# MM2_plates.net
KiCad netlist of a schematic drawn in EAGLE
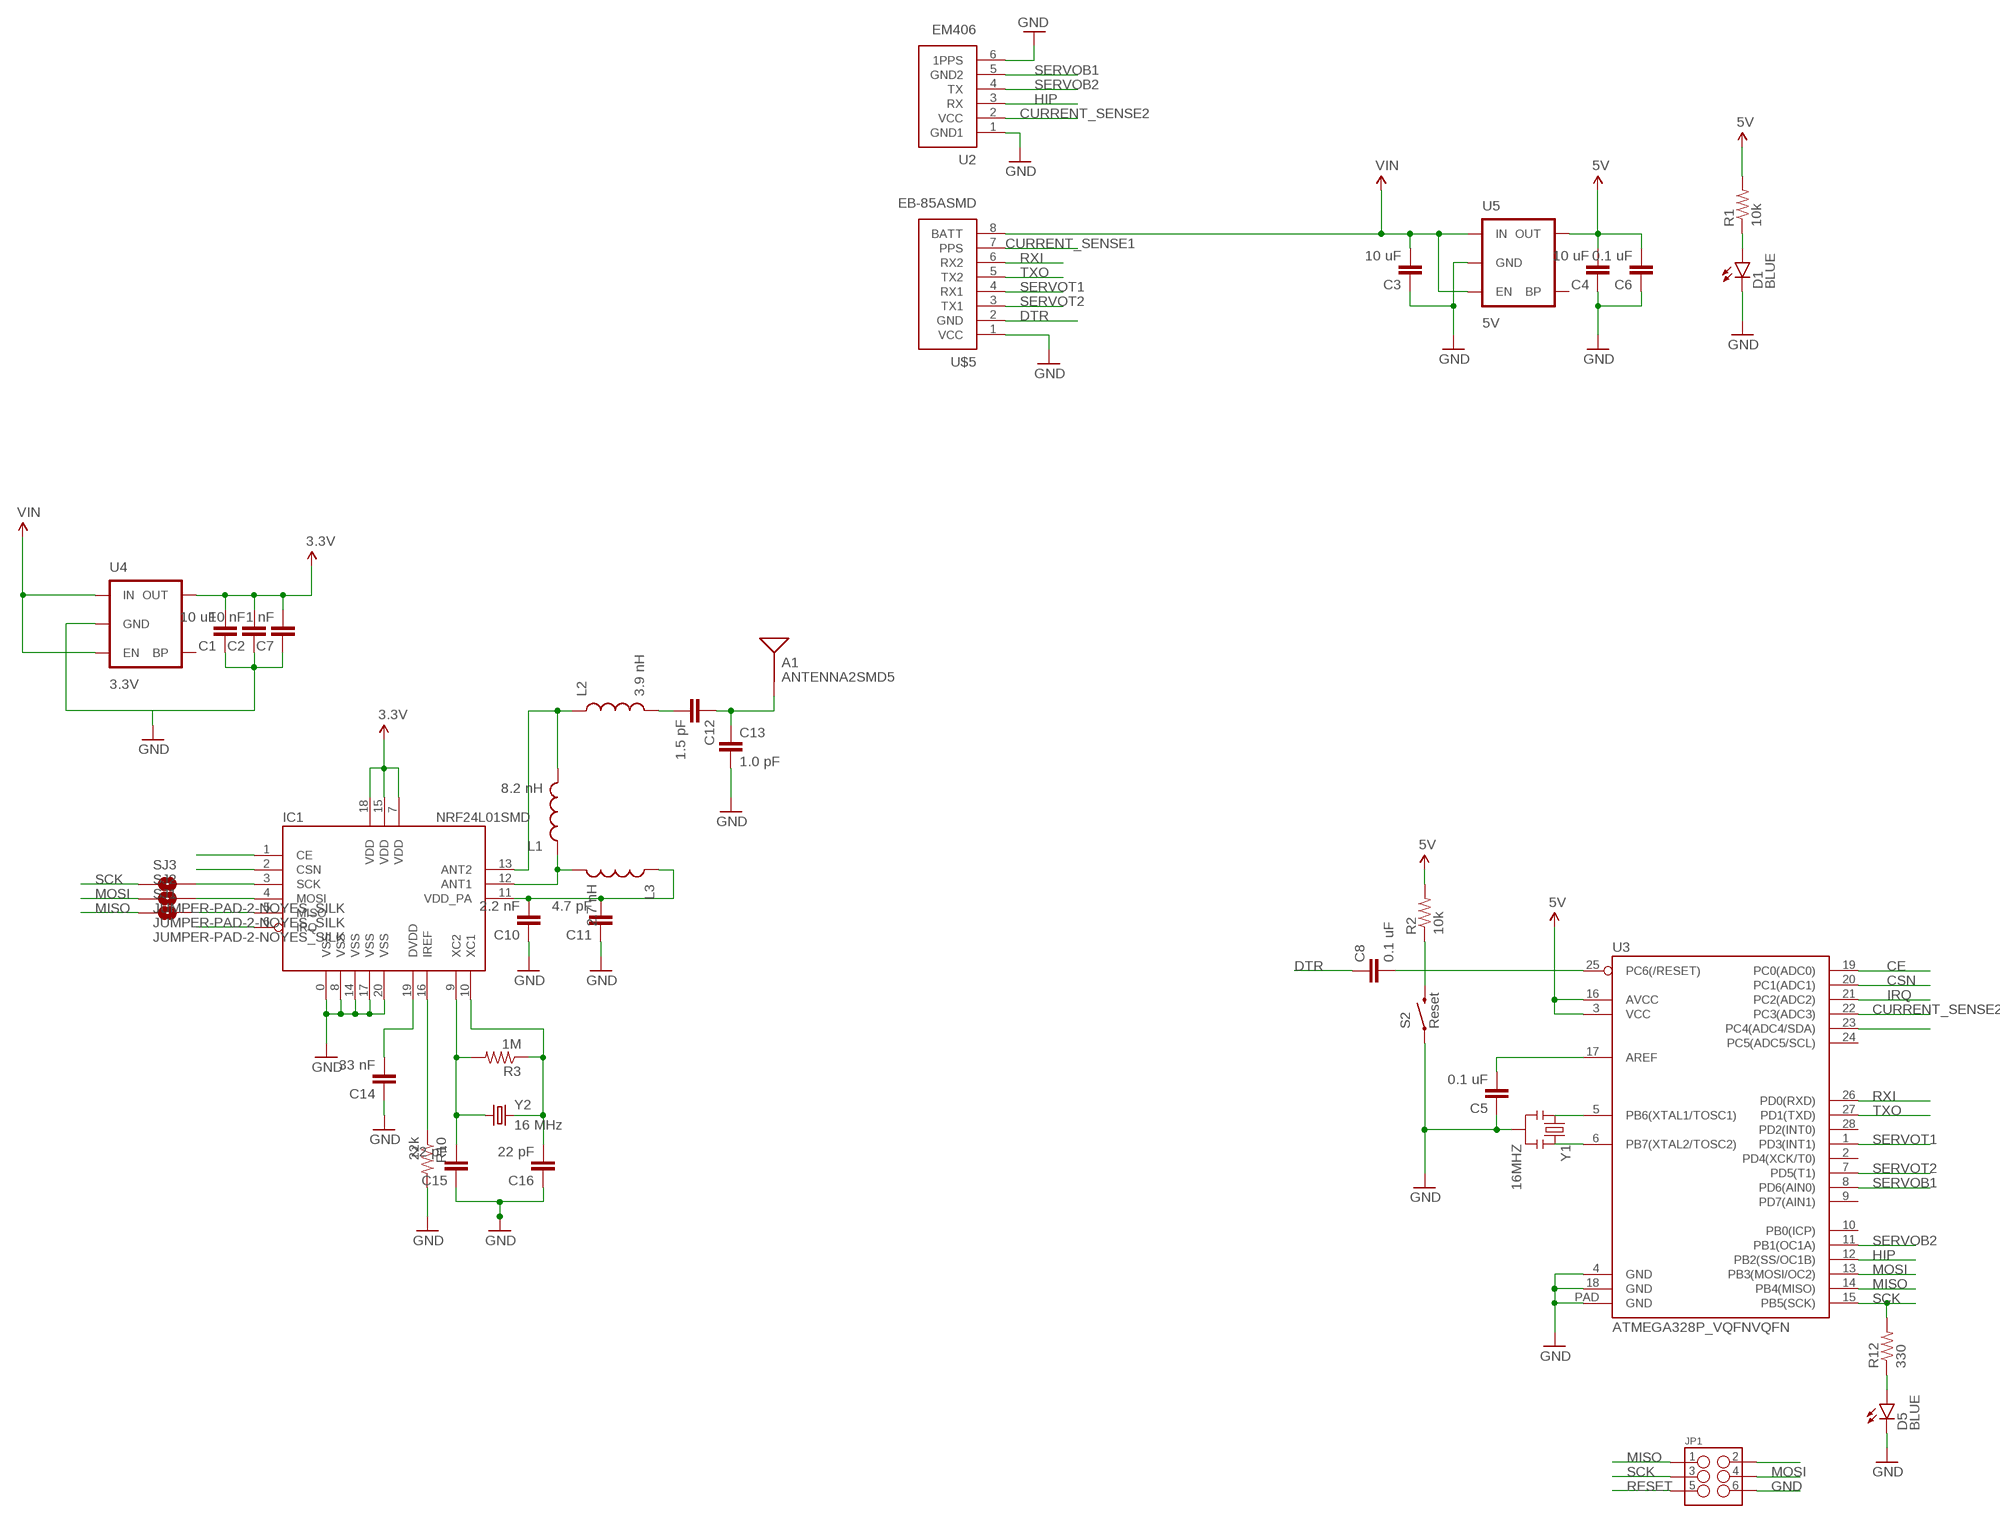
[diagram p0: schematic, sheet 1]

(export (version "E")
  (design (tool "Eeschema 10.0.6"))
  (components
    (comp (ref "A1")
      (value "ANTENNA2SMD5")
      (footprint "eagle-import:ANTENNA-CHIP5")
      (libsource (lib "eagle-import") (part "ANTENNA2SMD5"))
    )
    (comp (ref "C1")
      (value "10 uF")
      (footprint "eagle-import:0402-CAP")
      (libsource (lib "eagle-import") (part "CAP0402-CAP"))
    )
    (comp (ref "C2")
      (value "10 nF")
      (footprint "eagle-import:0402-CAP")
      (libsource (lib "eagle-import") (part "CAP0402-CAP"))
    )
    (comp (ref "C3")
      (value "10 uF")
      (footprint "eagle-import:0402-CAP")
      (libsource (lib "eagle-import") (part "CAP0402-CAP"))
    )
    (comp (ref "C4")
      (value "10 uF")
      (footprint "eagle-import:0402-CAP")
      (libsource (lib "eagle-import") (part "CAP0402-CAP"))
    )
    (comp (ref "C5")
      (value "0.1 uF")
      (footprint "eagle-import:0402-CAP")
      (libsource (lib "eagle-import") (part "CAP0402-CAP"))
    )
    (comp (ref "C6")
      (value "0.1 uF")
      (footprint "eagle-import:0402-CAP")
      (libsource (lib "eagle-import") (part "CAP0402-CAP"))
    )
    (comp (ref "C7")
      (value "1 nF")
      (footprint "eagle-import:0402-CAP")
      (libsource (lib "eagle-import") (part "CAP0402-CAP"))
    )
    (comp (ref "C8")
      (value "0.1 uF")
      (footprint "eagle-import:0402-CAP")
      (libsource (lib "eagle-import") (part "CAP0402-CAP"))
    )
    (comp (ref "C10")
      (value "2.2 nF")
      (footprint "eagle-import:0402-CAP")
      (libsource (lib "eagle-import") (part "CAP0402-CAP"))
    )
    (comp (ref "C11")
      (value "4.7 pF")
      (footprint "eagle-import:0402-CAP")
      (libsource (lib "eagle-import") (part "CAP0402-CAP"))
    )
    (comp (ref "C12")
      (value "1.5 pF")
      (footprint "eagle-import:0402-CAP")
      (libsource (lib "eagle-import") (part "CAP0402-CAP"))
    )
    (comp (ref "C13")
      (value "1.0 pF")
      (footprint "eagle-import:0402-CAP")
      (libsource (lib "eagle-import") (part "CAP0402-CAP"))
    )
    (comp (ref "C14")
      (value "33 nF")
      (footprint "eagle-import:0402-CAP")
      (libsource (lib "eagle-import") (part "CAP0402-CAP"))
    )
    (comp (ref "C15")
      (value "22 pF")
      (footprint "eagle-import:0402-CAP")
      (libsource (lib "eagle-import") (part "CAP0402-CAP"))
    )
    (comp (ref "C16")
      (value "22 pF")
      (footprint "eagle-import:0402-CAP")
      (libsource (lib "eagle-import") (part "CAP0402-CAP"))
    )
    (comp (ref "D1")
      (value "BLUE")
      (footprint "eagle-import:LED-0603")
      (libsource (lib "eagle-import") (part "LED-BLUE0603"))
    )
    (comp (ref "D5")
      (value "BLUE")
      (footprint "eagle-import:LED-0603")
      (libsource (lib "eagle-import") (part "LED-BLUE0603"))
    )
    (comp (ref "IC1")
      (value "NRF24L01SMD")
      (footprint "eagle-import:QFN20")
      (libsource (lib "eagle-import") (part "NRF24L01SMD"))
    )
    (comp (ref "JP1")
      (value "M03X2FEMALE_SMD")
      (footprint "eagle-import:2X3_SMD")
      (libsource (lib "eagle-import") (part "M03X2FEMALE_SMD"))
    )
    (comp (ref "L1")
      (value "8.2 nH")
      (footprint "eagle-import:C0402")
      (libsource (lib "eagle-import") (part "INDUCTOR0402"))
    )
    (comp (ref "L2")
      (value "3.9 nH")
      (footprint "eagle-import:C0402")
      (libsource (lib "eagle-import") (part "INDUCTOR0402"))
    )
    (comp (ref "L3")
      (value "2.7 nH")
      (footprint "eagle-import:C0402")
      (libsource (lib "eagle-import") (part "INDUCTOR0402"))
    )
    (comp (ref "R1")
      (value "10k")
      (footprint "eagle-import:0402-RES")
      (libsource (lib "eagle-import") (part "RESISTOR0402-RES"))
    )
    (comp (ref "R2")
      (value "10k")
      (footprint "eagle-import:0402-RES")
      (libsource (lib "eagle-import") (part "RESISTOR0402-RES"))
    )
    (comp (ref "R3")
      (value "1M")
      (footprint "eagle-import:0402-RES")
      (libsource (lib "eagle-import") (part "RESISTOR0402-RES"))
    )
    (comp (ref "R10")
      (value "22k")
      (footprint "eagle-import:0402-RES")
      (libsource (lib "eagle-import") (part "RESISTOR0402-RES"))
    )
    (comp (ref "R12")
      (value "330")
      (footprint "eagle-import:0402-RES")
      (libsource (lib "eagle-import") (part "RESISTOR0402-RES"))
    )
    (comp (ref "S2")
      (value "Reset")
      (footprint "eagle-import:TACTILE_SWITCH_SMD_4.6X2.8MM")
      (libsource (lib "eagle-import") (part "SWITCH-MOMENTARY-2SMD-4.6X2.8MM"))
    )
    (comp (ref "SJ1")
      (value "JUMPER-PAD-2-NOYES_SILK")
      (footprint "eagle-import:PAD-JUMPER-2-NO_YES_SILK")
      (libsource (lib "eagle-import") (part "JUMPER-PAD-2-NOYES_SILK"))
    )
    (comp (ref "SJ2")
      (value "JUMPER-PAD-2-NOYES_SILK")
      (footprint "eagle-import:PAD-JUMPER-2-NO_YES_SILK")
      (libsource (lib "eagle-import") (part "JUMPER-PAD-2-NOYES_SILK"))
    )
    (comp (ref "SJ3")
      (value "JUMPER-PAD-2-NOYES_SILK")
      (footprint "eagle-import:PAD-JUMPER-2-NO_YES_SILK")
      (libsource (lib "eagle-import") (part "JUMPER-PAD-2-NOYES_SILK"))
    )
    (comp (ref "U$5")
      (value "EB-85ASMD")
      (footprint "eagle-import:EB-85A")
      (libsource (lib "eagle-import") (part "EB-85ASMD"))
    )
    (comp (ref "U2")
      (value "EM406")
      (footprint "eagle-import:EM406")
      (libsource (lib "eagle-import") (part "EM406"))
    )
    (comp (ref "U3")
      (value "ATMEGA328P_VQFNVQFN")
      (footprint "eagle-import:VQFN-28")
      (libsource (lib "eagle-import") (part "ATMEGA328P_VQFNVQFN"))
    )
    (comp (ref "U4")
      (value "3.3V")
      (footprint "eagle-import:SOT23-5")
      (libsource (lib "eagle-import") (part "MIC52053.3V"))
    )
    (comp (ref "U5")
      (value "5V")
      (footprint "eagle-import:SOT23-5")
      (libsource (lib "eagle-import") (part "MIC52055V"))
    )
    (comp (ref "Y1")
      (value "16MHZ")
      (footprint "eagle-import:RESONATOR-SMD")
      (libsource (lib "eagle-import") (part "RESONATOR16MHZ"))
    )
    (comp (ref "Y2")
      (value "16 MHz")
      (footprint "eagle-import:CRYSTAL-SMD-5X3")
      (libsource (lib "eagle-import") (part "CRYSTAL5X3"))
    )
  )
  (nets
    (net (code "1") (name "/CE") (class "Default")
      (node (ref "IC1") (pin "1") (pinfunction "CE_1") (pintype "input"))
      (node (ref "U3") (pin "19") (pinfunction "PC0(ADC0)_19") (pintype "bidirectional"))
    )
    (net (code "2") (name "/CSN") (class "Default")
      (node (ref "IC1") (pin "2") (pinfunction "CSN_2") (pintype "input"))
      (node (ref "U3") (pin "20") (pinfunction "PC1(ADC1)_20") (pintype "bidirectional"))
    )
    (net (code "3") (name "/CURRENT_SENSE1") (class "Default")
      (node (ref "U$5") (pin "7") (pinfunction "PPS_7") (pintype "output"))
      (node (ref "U3") (pin "23") (pinfunction "PC4(ADC4/SDA)_23") (pintype "bidirectional"))
    )
    (net (code "4") (name "/CURRENT_SENSE2") (class "Default")
      (node (ref "U2") (pin "2") (pinfunction "VCC_2") (pintype "bidirectional"))
      (node (ref "U3") (pin "22") (pinfunction "PC3(ADC3)_22") (pintype "bidirectional"))
    )
    (net (code "5") (name "/DTR") (class "Default")
      (node (ref "C8") (pin "1") (pinfunction "1_1") (pintype "passive"))
      (node (ref "U$5") (pin "2") (pinfunction "GND_2") (pintype "power_in"))
    )
    (net (code "6") (name "/HIP") (class "Default")
      (node (ref "U2") (pin "3") (pinfunction "RX_3") (pintype "bidirectional"))
      (node (ref "U3") (pin "12") (pinfunction "PB2(SS/OC1B)_12") (pintype "bidirectional"))
    )
    (net (code "7") (name "/IRQ") (class "Default")
      (node (ref "IC1") (pin "6") (pinfunction "IRQ_6") (pintype "output"))
      (node (ref "U3") (pin "21") (pinfunction "PC2(ADC2)_21") (pintype "bidirectional"))
    )
    (net (code "8") (name "/MISO") (class "Default")
      (node (ref "JP1") (pin "1") (pinfunction "1_1") (pintype "bidirectional"))
      (node (ref "SJ1") (pin "1") (pinfunction "1_1") (pintype "passive"))
      (node (ref "U3") (pin "14") (pinfunction "PB4(MISO)_14") (pintype "bidirectional"))
    )
    (net (code "9") (name "/MOSI") (class "Default")
      (node (ref "JP1") (pin "4") (pinfunction "4_4") (pintype "bidirectional"))
      (node (ref "SJ2") (pin "1") (pinfunction "1_1") (pintype "passive"))
      (node (ref "U3") (pin "13") (pinfunction "PB3(MOSI/OC2)_13") (pintype "bidirectional"))
    )
    (net (code "10") (name "/RESET") (class "Default")
      (node (ref "C8") (pin "2") (pinfunction "2_2") (pintype "passive"))
      (node (ref "JP1") (pin "5") (pinfunction "5_5") (pintype "bidirectional"))
      (node (ref "R2") (pin "1") (pinfunction "1_1") (pintype "passive"))
      (node (ref "S2") (pin "3") (pinfunction "2_3") (pintype "passive"))
      (node (ref "S2") (pin "4") (pinfunction "2_4") (pintype "passive"))
      (node (ref "U3") (pin "25") (pinfunction "PC6(/RESET)_25") (pintype "bidirectional"))
    )
    (net (code "11") (name "/RXI") (class "Default")
      (node (ref "U$5") (pin "6") (pinfunction "RX2_6") (pintype "input"))
      (node (ref "U3") (pin "26") (pinfunction "PD0(RXD)_26") (pintype "bidirectional"))
    )
    (net (code "12") (name "/SCK") (class "Default")
      (node (ref "JP1") (pin "3") (pinfunction "3_3") (pintype "bidirectional"))
      (node (ref "R12") (pin "2") (pinfunction "2_2") (pintype "passive"))
      (node (ref "SJ3") (pin "1") (pinfunction "1_1") (pintype "passive"))
      (node (ref "U3") (pin "15") (pinfunction "PB5(SCK)_15") (pintype "bidirectional"))
    )
    (net (code "13") (name "/SERVOB1") (class "Default")
      (node (ref "U2") (pin "5") (pinfunction "GND2_5") (pintype "bidirectional"))
      (node (ref "U3") (pin "8") (pinfunction "PD6(AIN0)_8") (pintype "bidirectional"))
    )
    (net (code "14") (name "/SERVOB2") (class "Default")
      (node (ref "U2") (pin "4") (pinfunction "TX_4") (pintype "bidirectional"))
      (node (ref "U3") (pin "11") (pinfunction "PB1(OC1A)_11") (pintype "bidirectional"))
    )
    (net (code "15") (name "/SERVOT1") (class "Default")
      (node (ref "U$5") (pin "4") (pinfunction "RX1_4") (pintype "input"))
      (node (ref "U3") (pin "1") (pinfunction "PD3(INT1)_1") (pintype "bidirectional"))
    )
    (net (code "16") (name "/SERVOT2") (class "Default")
      (node (ref "U$5") (pin "3") (pinfunction "TX1_3") (pintype "output"))
      (node (ref "U3") (pin "7") (pinfunction "PD5(T1)_7") (pintype "bidirectional"))
    )
    (net (code "17") (name "/TXO") (class "Default")
      (node (ref "U$5") (pin "5") (pinfunction "TX2_5") (pintype "output"))
      (node (ref "U3") (pin "27") (pinfunction "PD1(TXD)_27") (pintype "bidirectional"))
    )
    (net (code "18") (name "3.3V") (class "Default")
      (node (ref "C1") (pin "2") (pinfunction "2_2") (pintype "passive"))
      (node (ref "C2") (pin "2") (pinfunction "2_2") (pintype "passive"))
      (node (ref "C7") (pin "2") (pinfunction "2_2") (pintype "passive"))
      (node (ref "IC1") (pin "15") (pinfunction "VDD_15") (pintype "power_in"))
      (node (ref "IC1") (pin "18") (pinfunction "VDD_18") (pintype "power_in"))
      (node (ref "IC1") (pin "7") (pinfunction "VDD_7") (pintype "power_in"))
      (node (ref "U4") (pin "5") (pinfunction "OUT_5") (pintype "passive"))
    )
    (net (code "19") (name "5V") (class "Default")
      (node (ref "C4") (pin "2") (pinfunction "2_2") (pintype "passive"))
      (node (ref "C6") (pin "2") (pinfunction "2_2") (pintype "passive"))
      (node (ref "JP1") (pin "2") (pinfunction "2_2") (pintype "bidirectional"))
      (node (ref "R1") (pin "2") (pinfunction "2_2") (pintype "passive"))
      (node (ref "R2") (pin "2") (pinfunction "2_2") (pintype "passive"))
      (node (ref "U3") (pin "16") (pinfunction "AVCC_16") (pintype "bidirectional"))
      (node (ref "U3") (pin "3") (pinfunction "VCC_3") (pintype "bidirectional"))
      (node (ref "U5") (pin "5") (pinfunction "OUT_5") (pintype "passive"))
    )
    (net (code "20") (name "GND") (class "Default")
      (node (ref "C1") (pin "1") (pinfunction "1_1") (pintype "passive"))
      (node (ref "C10") (pin "1") (pinfunction "1_1") (pintype "passive"))
      (node (ref "C11") (pin "1") (pinfunction "1_1") (pintype "passive"))
      (node (ref "C13") (pin "2") (pinfunction "2_2") (pintype "passive"))
      (node (ref "C14") (pin "1") (pinfunction "1_1") (pintype "passive"))
      (node (ref "C15") (pin "1") (pinfunction "1_1") (pintype "passive"))
      (node (ref "C16") (pin "1") (pinfunction "1_1") (pintype "passive"))
      (node (ref "C2") (pin "1") (pinfunction "1_1") (pintype "passive"))
      (node (ref "C3") (pin "1") (pinfunction "1_1") (pintype "passive"))
      (node (ref "C4") (pin "1") (pinfunction "1_1") (pintype "passive"))
      (node (ref "C5") (pin "1") (pinfunction "1_1") (pintype "passive"))
      (node (ref "C6") (pin "1") (pinfunction "1_1") (pintype "passive"))
      (node (ref "C7") (pin "1") (pinfunction "1_1") (pintype "passive"))
      (node (ref "D1") (pin "C") (pinfunction "C_C") (pintype "passive"))
      (node (ref "D5") (pin "C") (pinfunction "C_C") (pintype "passive"))
      (node (ref "IC1") (pin "0") (pinfunction "VSS_0") (pintype "power_in"))
      (node (ref "IC1") (pin "14") (pinfunction "VSS_14") (pintype "power_in"))
      (node (ref "IC1") (pin "17") (pinfunction "VSS_17") (pintype "power_in"))
      (node (ref "IC1") (pin "20") (pinfunction "VSS_20") (pintype "power_in"))
      (node (ref "IC1") (pin "8") (pinfunction "VSS_8") (pintype "power_in"))
      (node (ref "JP1") (pin "6") (pinfunction "6_6") (pintype "bidirectional"))
      (node (ref "R10") (pin "2") (pinfunction "2_2") (pintype "passive"))
      (node (ref "S2") (pin "1") (pinfunction "1_1") (pintype "passive"))
      (node (ref "S2") (pin "2") (pinfunction "1_2") (pintype "passive"))
      (node (ref "U$5") (pin "1") (pinfunction "VCC_1") (pintype "power_in"))
      (node (ref "U2") (pin "1") (pinfunction "GND1_1") (pintype "bidirectional"))
      (node (ref "U2") (pin "6") (pinfunction "1PPS_6") (pintype "bidirectional"))
      (node (ref "U3") (pin "18") (pinfunction "GND_18") (pintype "bidirectional"))
      (node (ref "U3") (pin "4") (pinfunction "GND_4") (pintype "bidirectional"))
      (node (ref "U3") (pin "PAD") (pinfunction "GND_PAD") (pintype "bidirectional"))
      (node (ref "U4") (pin "2") (pinfunction "GND_2") (pintype "input"))
      (node (ref "U5") (pin "2") (pinfunction "GND_2") (pintype "input"))
      (node (ref "Y1") (pin "2") (pinfunction "2_2") (pintype "passive"))
    )
    (net (code "21") (name "Net-(A1-SIGNAL)") (class "Default")
      (node (ref "A1") (pin "FEED") (pinfunction "SIGNAL_FEED") (pintype "bidirectional"))
      (node (ref "C12") (pin "1") (pinfunction "1_1") (pintype "passive"))
      (node (ref "C13") (pin "1") (pinfunction "1_1") (pintype "passive"))
    )
    (net (code "22") (name "Net-(C12-Pad2)") (class "Default")
      (node (ref "C12") (pin "2") (pinfunction "2_2") (pintype "passive"))
      (node (ref "L2") (pin "2") (pinfunction "2_2") (pintype "passive"))
    )
    (net (code "23") (name "Net-(D1-PadA)") (class "Default")
      (node (ref "D1") (pin "A") (pinfunction "A_A") (pintype "passive"))
      (node (ref "R1") (pin "1") (pinfunction "1_1") (pintype "passive"))
    )
    (net (code "24") (name "Net-(D5-PadA)") (class "Default")
      (node (ref "D5") (pin "A") (pinfunction "A_A") (pintype "passive"))
      (node (ref "R12") (pin "1") (pinfunction "1_1") (pintype "passive"))
    )
    (net (code "25") (name "Net-(IC1-ANT1)") (class "Default")
      (node (ref "IC1") (pin "12") (pinfunction "ANT1_12") (pintype "output"))
      (node (ref "L1") (pin "1") (pinfunction "1_1") (pintype "passive"))
      (node (ref "L3") (pin "2") (pinfunction "2_2") (pintype "passive"))
    )
    (net (code "26") (name "Net-(IC1-ANT2)") (class "Default")
      (node (ref "IC1") (pin "13") (pinfunction "ANT2_13") (pintype "output"))
      (node (ref "L1") (pin "2") (pinfunction "2_2") (pintype "passive"))
      (node (ref "L2") (pin "1") (pinfunction "1_1") (pintype "passive"))
    )
    (net (code "27") (name "Net-(IC1-DVDD)") (class "Default")
      (node (ref "C14") (pin "2") (pinfunction "2_2") (pintype "passive"))
      (node (ref "IC1") (pin "19") (pinfunction "DVDD_19") (pintype "power_in"))
    )
    (net (code "28") (name "Net-(IC1-IREF)") (class "Default")
      (node (ref "IC1") (pin "16") (pinfunction "IREF_16") (pintype "input"))
      (node (ref "R10") (pin "1") (pinfunction "1_1") (pintype "passive"))
    )
    (net (code "29") (name "Net-(IC1-MISO)") (class "Default")
      (node (ref "IC1") (pin "5") (pinfunction "MISO_5") (pintype "output"))
      (node (ref "SJ1") (pin "2") (pinfunction "2_2") (pintype "passive"))
    )
    (net (code "30") (name "Net-(IC1-MOSI)") (class "Default")
      (node (ref "IC1") (pin "4") (pinfunction "MOSI_4") (pintype "input"))
      (node (ref "SJ2") (pin "2") (pinfunction "2_2") (pintype "passive"))
    )
    (net (code "31") (name "Net-(IC1-SCK)") (class "Default")
      (node (ref "IC1") (pin "3") (pinfunction "SCK_3") (pintype "input"))
      (node (ref "SJ3") (pin "2") (pinfunction "2_2") (pintype "passive"))
    )
    (net (code "32") (name "Net-(IC1-VDD_PA)") (class "Default")
      (node (ref "C10") (pin "2") (pinfunction "2_2") (pintype "passive"))
      (node (ref "C11") (pin "2") (pinfunction "2_2") (pintype "passive"))
      (node (ref "IC1") (pin "11") (pinfunction "VDD_PA_11") (pintype "power_in"))
      (node (ref "L3") (pin "1") (pinfunction "1_1") (pintype "passive"))
    )
    (net (code "33") (name "Net-(IC1-XC1)") (class "Default")
      (node (ref "C16") (pin "2") (pinfunction "2_2") (pintype "passive"))
      (node (ref "IC1") (pin "10") (pinfunction "XC1_10") (pintype "input"))
      (node (ref "R3") (pin "1") (pinfunction "1_1") (pintype "passive"))
      (node (ref "Y2") (pin "3") (pinfunction "2_3") (pintype "passive"))
    )
    (net (code "34") (name "Net-(IC1-XC2)") (class "Default")
      (node (ref "C15") (pin "2") (pinfunction "2_2") (pintype "passive"))
      (node (ref "IC1") (pin "9") (pinfunction "XC2_9") (pintype "input"))
      (node (ref "R3") (pin "2") (pinfunction "2_2") (pintype "passive"))
      (node (ref "Y2") (pin "1") (pinfunction "1_1") (pintype "passive"))
    )
    (net (code "35") (name "Net-(U3-AREF)") (class "Default")
      (node (ref "C5") (pin "2") (pinfunction "2_2") (pintype "passive"))
      (node (ref "U3") (pin "17") (pinfunction "AREF_17") (pintype "bidirectional"))
    )
    (net (code "36") (name "Net-(U3-PB6(XTAL1{slash}TOSC1))") (class "Default")
      (node (ref "U3") (pin "5") (pinfunction "PB6(XTAL1/TOSC1)_5") (pintype "bidirectional"))
      (node (ref "Y1") (pin "1") (pinfunction "1_1") (pintype "passive"))
    )
    (net (code "37") (name "Net-(U3-PB7(XTAL2{slash}TOSC2))") (class "Default")
      (node (ref "U3") (pin "6") (pinfunction "PB7(XTAL2/TOSC2)_6") (pintype "bidirectional"))
      (node (ref "Y1") (pin "3") (pinfunction "3_3") (pintype "passive"))
    )
    (net (code "38") (name "VIN") (class "Default")
      (node (ref "C3") (pin "2") (pinfunction "2_2") (pintype "passive"))
      (node (ref "U$5") (pin "8") (pinfunction "BATT_8") (pintype "power_in"))
      (node (ref "U4") (pin "1") (pinfunction "IN_1") (pintype "input"))
      (node (ref "U4") (pin "3") (pinfunction "EN_3") (pintype "input"))
      (node (ref "U5") (pin "1") (pinfunction "IN_1") (pintype "input"))
      (node (ref "U5") (pin "3") (pinfunction "EN_3") (pintype "input"))
    )
    (net (code "39") (name "unconnected-(U3-PB0(ICP)-Pad10)") (class "Default")
      (node (ref "U3") (pin "10") (pinfunction "PB0(ICP)_10") (pintype "bidirectional"))
    )
    (net (code "40") (name "unconnected-(U3-PC5(ADC5{slash}SCL)-Pad24)") (class "Default")
      (node (ref "U3") (pin "24") (pinfunction "PC5(ADC5/SCL)_24") (pintype "bidirectional"))
    )
    (net (code "41") (name "unconnected-(U3-PD2(INT0)-Pad28)") (class "Default")
      (node (ref "U3") (pin "28") (pinfunction "PD2(INT0)_28") (pintype "bidirectional"))
    )
    (net (code "42") (name "unconnected-(U3-PD4(XCK{slash}T0)-Pad2)") (class "Default")
      (node (ref "U3") (pin "2") (pinfunction "PD4(XCK/T0)_2") (pintype "bidirectional"))
    )
    (net (code "43") (name "unconnected-(U3-PD7(AIN1)-Pad9)") (class "Default")
      (node (ref "U3") (pin "9") (pinfunction "PD7(AIN1)_9") (pintype "bidirectional"))
    )
    (net (code "44") (name "unconnected-(U4-BP-Pad4)") (class "Default")
      (node (ref "U4") (pin "4") (pinfunction "BP_4") (pintype "input"))
    )
    (net (code "45") (name "unconnected-(U5-BP-Pad4)") (class "Default")
      (node (ref "U5") (pin "4") (pinfunction "BP_4") (pintype "input"))
    )
  )
)
